# grissom_r1.net
KiCad netlist of a schematic drawn in EAGLE
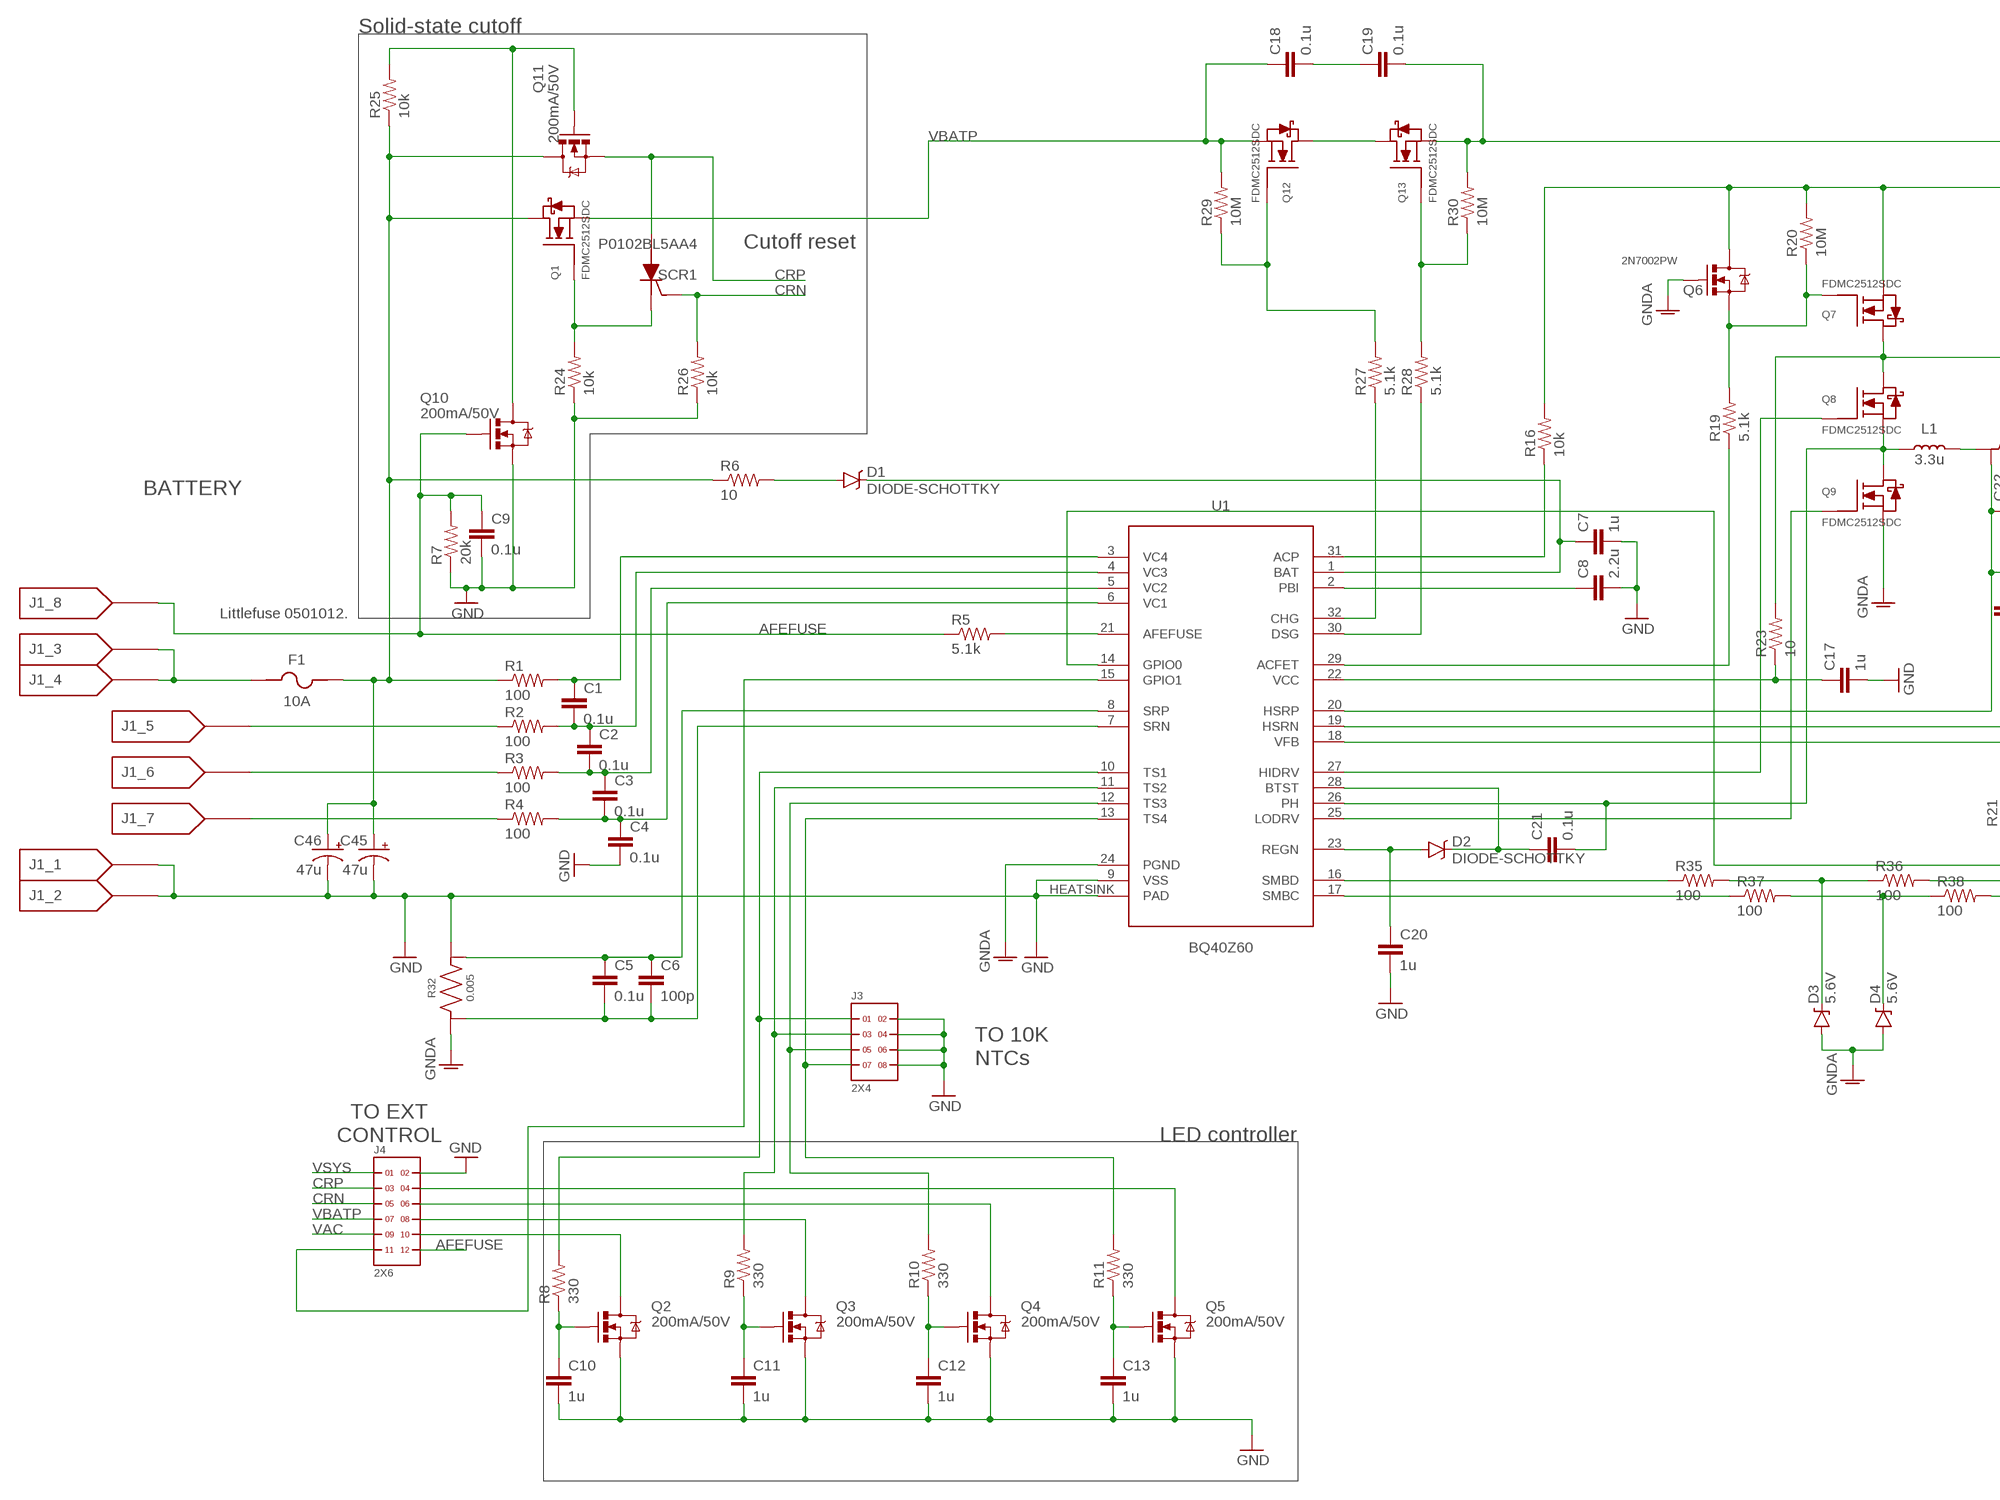
[diagram p0: schematic, sheet 1, part 1 of 2]
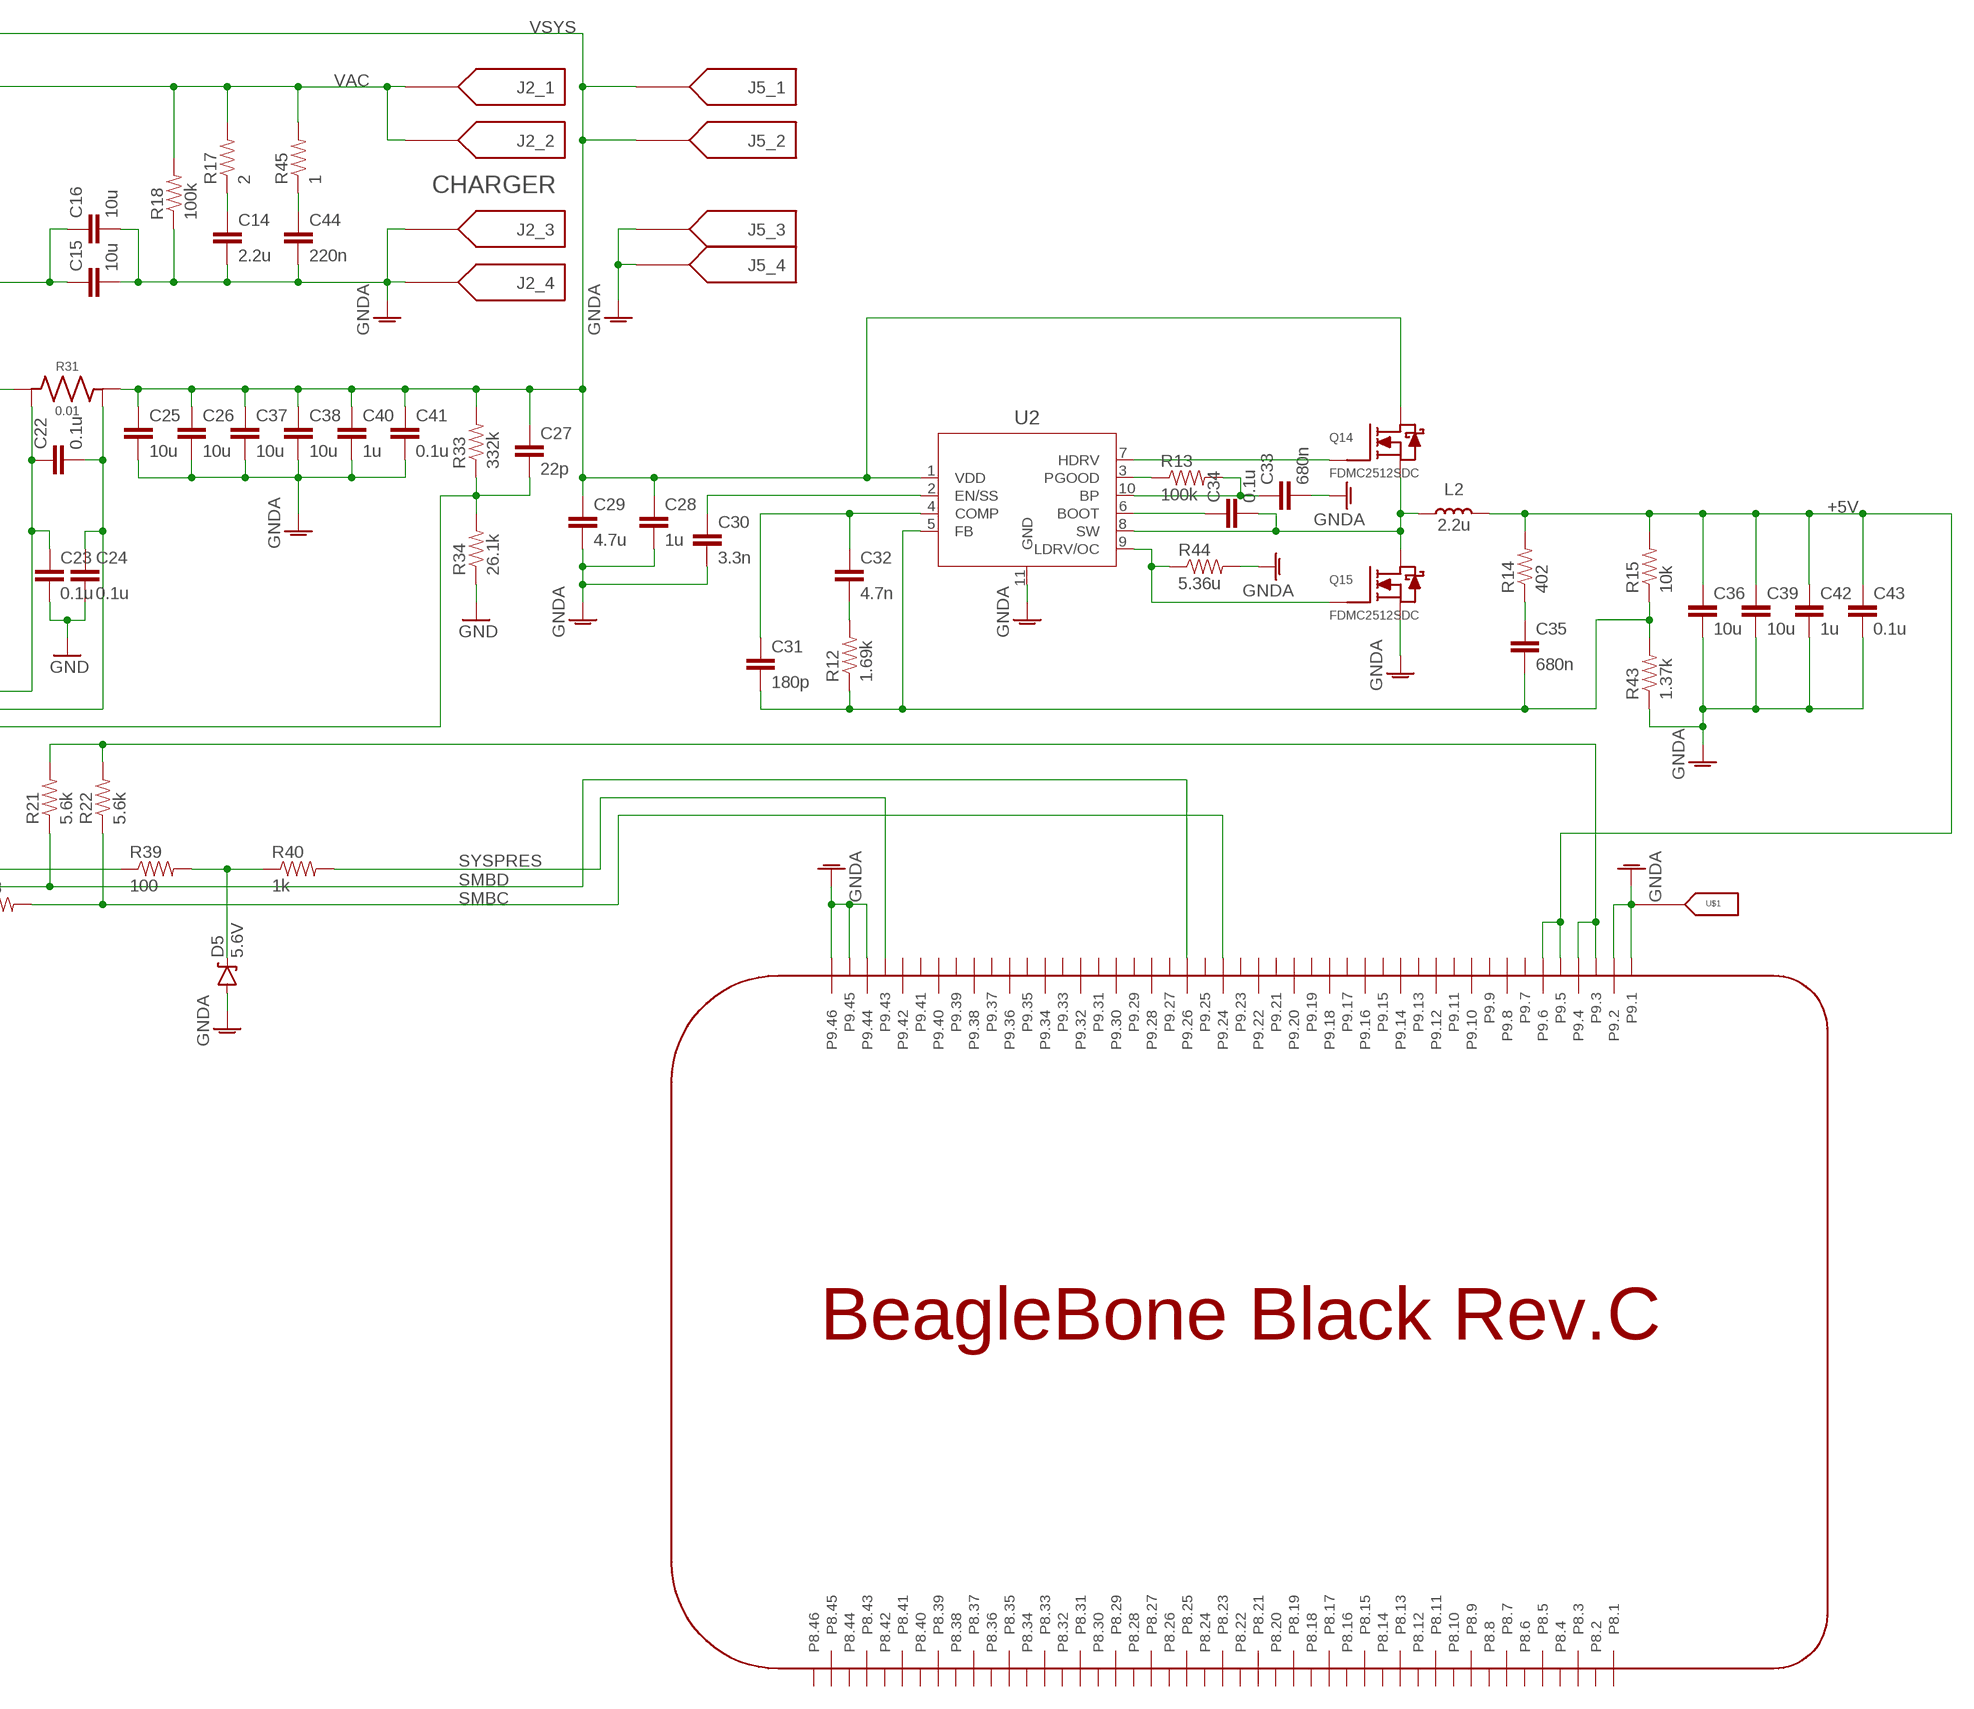
[diagram p1: schematic, sheet 1, part 2 of 2]

(export (version "E")
  (design (tool "Eeschema 10.0.6"))
  (components
    (comp (ref "C1")
      (value "0.1u")
      (footprint "eagle-import:0805")
      (libsource (lib "eagle-import") (part "CAP0805"))
    )
    (comp (ref "C2")
      (value "0.1u")
      (footprint "eagle-import:0805")
      (libsource (lib "eagle-import") (part "CAP0805"))
    )
    (comp (ref "C3")
      (value "0.1u")
      (footprint "eagle-import:0805")
      (libsource (lib "eagle-import") (part "CAP0805"))
    )
    (comp (ref "C4")
      (value "0.1u")
      (footprint "eagle-import:0805")
      (libsource (lib "eagle-import") (part "CAP0805"))
    )
    (comp (ref "C5")
      (value "0.1u")
      (footprint "eagle-import:0805")
      (libsource (lib "eagle-import") (part "CAP0805"))
    )
    (comp (ref "C6")
      (value "100p")
      (footprint "eagle-import:0805")
      (libsource (lib "eagle-import") (part "CAP0805"))
    )
    (comp (ref "C7")
      (value "1u")
      (footprint "eagle-import:0805")
      (libsource (lib "eagle-import") (part "CAP0805"))
    )
    (comp (ref "C8")
      (value "2.2u")
      (footprint "eagle-import:0805")
      (libsource (lib "eagle-import") (part "CAP0805"))
    )
    (comp (ref "C9")
      (value "0.1u")
      (footprint "eagle-import:0805")
      (libsource (lib "eagle-import") (part "CAP0805"))
    )
    (comp (ref "C10")
      (value "1u")
      (footprint "eagle-import:0805")
      (libsource (lib "eagle-import") (part "CAP0805"))
    )
    (comp (ref "C11")
      (value "1u")
      (footprint "eagle-import:0805")
      (libsource (lib "eagle-import") (part "CAP0805"))
    )
    (comp (ref "C12")
      (value "1u")
      (footprint "eagle-import:0805")
      (libsource (lib "eagle-import") (part "CAP0805"))
    )
    (comp (ref "C13")
      (value "1u")
      (footprint "eagle-import:0805")
      (libsource (lib "eagle-import") (part "CAP0805"))
    )
    (comp (ref "C14")
      (value "2.2u")
      (footprint "eagle-import:0805")
      (libsource (lib "eagle-import") (part "CAP0805"))
    )
    (comp (ref "C15")
      (value "10u")
      (footprint "eagle-import:1206")
      (libsource (lib "eagle-import") (part "CAP1206"))
    )
    (comp (ref "C16")
      (value "10u")
      (footprint "eagle-import:1206")
      (libsource (lib "eagle-import") (part "CAP1206"))
    )
    (comp (ref "C17")
      (value "1u")
      (footprint "eagle-import:0805")
      (libsource (lib "eagle-import") (part "CAP0805"))
    )
    (comp (ref "C18")
      (value "0.1u")
      (footprint "eagle-import:0805")
      (libsource (lib "eagle-import") (part "CAP0805"))
    )
    (comp (ref "C19")
      (value "0.1u")
      (footprint "eagle-import:0805")
      (libsource (lib "eagle-import") (part "CAP0805"))
    )
    (comp (ref "C20")
      (value "1u")
      (footprint "eagle-import:0805")
      (libsource (lib "eagle-import") (part "CAP0805"))
    )
    (comp (ref "C21")
      (value "0.1u")
      (footprint "eagle-import:0805")
      (libsource (lib "eagle-import") (part "CAP0805"))
    )
    (comp (ref "C22")
      (value "0.1u")
      (footprint "eagle-import:0805")
      (libsource (lib "eagle-import") (part "CAP0805"))
    )
    (comp (ref "C23")
      (value "0.1u")
      (footprint "eagle-import:0805")
      (libsource (lib "eagle-import") (part "CAP0805"))
    )
    (comp (ref "C24")
      (value "0.1u")
      (footprint "eagle-import:0805")
      (libsource (lib "eagle-import") (part "CAP0805"))
    )
    (comp (ref "C25")
      (value "10u")
      (footprint "eagle-import:1206")
      (libsource (lib "eagle-import") (part "CAP1206"))
    )
    (comp (ref "C26")
      (value "10u")
      (footprint "eagle-import:1206")
      (libsource (lib "eagle-import") (part "CAP1206"))
    )
    (comp (ref "C27")
      (value "22p")
      (footprint "eagle-import:0805")
      (libsource (lib "eagle-import") (part "CAP0805"))
    )
    (comp (ref "C28")
      (value "1u")
      (footprint "eagle-import:0805")
      (libsource (lib "eagle-import") (part "CAP0805"))
    )
    (comp (ref "C29")
      (value "4.7u")
      (footprint "eagle-import:0805")
      (libsource (lib "eagle-import") (part "CAP0805"))
    )
    (comp (ref "C30")
      (value "3.3n")
      (footprint "eagle-import:0805")
      (libsource (lib "eagle-import") (part "CAP0805"))
    )
    (comp (ref "C31")
      (value "180p")
      (footprint "eagle-import:0805")
      (libsource (lib "eagle-import") (part "CAP0805"))
    )
    (comp (ref "C32")
      (value "4.7n")
      (footprint "eagle-import:0805")
      (libsource (lib "eagle-import") (part "CAP0805"))
    )
    (comp (ref "C33")
      (value "680n")
      (footprint "eagle-import:0805")
      (libsource (lib "eagle-import") (part "CAP0805"))
    )
    (comp (ref "C34")
      (value "0.1u")
      (footprint "eagle-import:0805")
      (libsource (lib "eagle-import") (part "CAP0805"))
    )
    (comp (ref "C35")
      (value "680n")
      (footprint "eagle-import:0805")
      (libsource (lib "eagle-import") (part "CAP0805"))
    )
    (comp (ref "C36")
      (value "10u")
      (footprint "eagle-import:1206")
      (libsource (lib "eagle-import") (part "CAP1206"))
    )
    (comp (ref "C37")
      (value "10u")
      (footprint "eagle-import:1206")
      (libsource (lib "eagle-import") (part "CAP1206"))
    )
    (comp (ref "C38")
      (value "10u")
      (footprint "eagle-import:1206")
      (libsource (lib "eagle-import") (part "CAP1206"))
    )
    (comp (ref "C39")
      (value "10u")
      (footprint "eagle-import:1206")
      (libsource (lib "eagle-import") (part "CAP1206"))
    )
    (comp (ref "C40")
      (value "1u")
      (footprint "eagle-import:1206")
      (libsource (lib "eagle-import") (part "CAP1206"))
    )
    (comp (ref "C41")
      (value "0.1u")
      (footprint "eagle-import:1206")
      (libsource (lib "eagle-import") (part "CAP1206"))
    )
    (comp (ref "C42")
      (value "1u")
      (footprint "eagle-import:1206")
      (libsource (lib "eagle-import") (part "CAP1206"))
    )
    (comp (ref "C43")
      (value "0.1u")
      (footprint "eagle-import:1206")
      (libsource (lib "eagle-import") (part "CAP1206"))
    )
    (comp (ref "C44")
      (value "220n")
      (footprint "eagle-import:0805")
      (libsource (lib "eagle-import") (part "CAP0805"))
    )
    (comp (ref "C45")
      (value "47u")
      (footprint "eagle-import:CPOL-RADIAL-10UF-25V")
      (libsource (lib "eagle-import") (part "CAP_POLPTH2"))
    )
    (comp (ref "C46")
      (value "47u")
      (footprint "eagle-import:CPOL-RADIAL-10UF-25V")
      (libsource (lib "eagle-import") (part "CAP_POLPTH2"))
    )
    (comp (ref "D1")
      (value "DIODE-SCHOTTKY")
      (footprint "eagle-import:SOT23-3")
      (libsource (lib "eagle-import") (part "DIODE-SCHOTTKY"))
    )
    (comp (ref "D2")
      (value "DIODE-SCHOTTKY")
      (footprint "eagle-import:SOT23-3")
      (libsource (lib "eagle-import") (part "DIODE-SCHOTTKY"))
    )
    (comp (ref "D3")
      (value "5.6V")
      (footprint "eagle-import:SOD-323")
      (libsource (lib "eagle-import") (part "DIODE-ZENER5.6V"))
    )
    (comp (ref "D4")
      (value "5.6V")
      (footprint "eagle-import:SOD-323")
      (libsource (lib "eagle-import") (part "DIODE-ZENER5.6V"))
    )
    (comp (ref "D5")
      (value "5.6V")
      (footprint "eagle-import:SOD-323")
      (libsource (lib "eagle-import") (part "DIODE-ZENER5.6V"))
    )
    (comp (ref "F1")
      (value "10A")
      (footprint "eagle-import:LITTELFUSE_501")
      (libsource (lib "eagle-import") (part "LITTELFUSE_501"))
    )
    (comp (ref "J1")
      (value "105314-X208")
      (footprint "eagle-import:105314-X208")
      (libsource (lib "eagle-import") (part "105314-X208"))
    )
    (comp (ref "J2")
      (value "105314-X204")
      (footprint "eagle-import:105314-X204")
      (libsource (lib "eagle-import") (part "105314-X204"))
    )
    (comp (ref "J3")
      (value "2X4")
      (footprint "eagle-import:2X4")
      (libsource (lib "eagle-import") (part "2X4"))
    )
    (comp (ref "J4")
      (value "2X6")
      (footprint "eagle-import:2X6")
      (libsource (lib "eagle-import") (part "2X6"))
    )
    (comp (ref "J5")
      (value "105314-X204")
      (footprint "eagle-import:105314-X204")
      (libsource (lib "eagle-import") (part "105314-X204"))
    )
    (comp (ref "L1")
      (value "3.3u")
      (footprint "eagle-import:BOURNS_SRP7028A")
      (libsource (lib "eagle-import") (part "BOURNS_SRP7028A"))
    )
    (comp (ref "L2")
      (value "2.2u")
      (footprint "eagle-import:BOURNS_SRP7028A")
      (libsource (lib "eagle-import") (part "BOURNS_SRP7028A"))
    )
    (comp (ref "PCB1")
      (value "BEAGLEBONE_BLACK_BLANK")
      (footprint "eagle-import:BEAGLEBONE_BLACK_BLANK")
      (libsource (lib "eagle-import") (part "BEAGLEBONE_BLACK_BLANK"))
    )
    (comp (ref "Q1")
      (value "FDMC2512SDC")
      (footprint "eagle-import:MO240")
      (libsource (lib "eagle-import") (part "FDMC2512SDC"))
    )
    (comp (ref "Q2")
      (value "200mA/50V")
      (footprint "eagle-import:SOT23-3")
      (libsource (lib "eagle-import") (part "MOSFET-NCHANNELBSS138"))
    )
    (comp (ref "Q3")
      (value "200mA/50V")
      (footprint "eagle-import:SOT23-3")
      (libsource (lib "eagle-import") (part "MOSFET-NCHANNELBSS138"))
    )
    (comp (ref "Q4")
      (value "200mA/50V")
      (footprint "eagle-import:SOT23-3")
      (libsource (lib "eagle-import") (part "MOSFET-NCHANNELBSS138"))
    )
    (comp (ref "Q5")
      (value "200mA/50V")
      (footprint "eagle-import:SOT23-3")
      (libsource (lib "eagle-import") (part "MOSFET-NCHANNELBSS138"))
    )
    (comp (ref "Q6")
      (value "2N7002PW")
      (footprint "eagle-import:SOT323")
      (libsource (lib "eagle-import") (part "MOSFET-NCHANNEL2N7002PW"))
    )
    (comp (ref "Q7")
      (value "FDMC2512SDC")
      (footprint "eagle-import:MO240")
      (libsource (lib "eagle-import") (part "FDMC2512SDC"))
    )
    (comp (ref "Q8")
      (value "FDMC2512SDC")
      (footprint "eagle-import:MO240")
      (libsource (lib "eagle-import") (part "FDMC2512SDC"))
    )
    (comp (ref "Q9")
      (value "FDMC2512SDC")
      (footprint "eagle-import:MO240")
      (libsource (lib "eagle-import") (part "FDMC2512SDC"))
    )
    (comp (ref "Q10")
      (value "200mA/50V")
      (footprint "eagle-import:SOT23-3")
      (libsource (lib "eagle-import") (part "MOSFET-NCHANNELBSS138"))
    )
    (comp (ref "Q11")
      (value "200mA/50V")
      (footprint "eagle-import:SOT23-3")
      (libsource (lib "eagle-import") (part "MOSFET-NCHANNELBSS138"))
    )
    (comp (ref "Q12")
      (value "FDMC2512SDC")
      (footprint "eagle-import:MO240")
      (libsource (lib "eagle-import") (part "FDMC2512SDC"))
    )
    (comp (ref "Q13")
      (value "FDMC2512SDC")
      (footprint "eagle-import:MO240")
      (libsource (lib "eagle-import") (part "FDMC2512SDC"))
    )
    (comp (ref "Q14")
      (value "FDMC2512SDC")
      (footprint "eagle-import:MO240")
      (libsource (lib "eagle-import") (part "FDMC2512SDC"))
    )
    (comp (ref "Q15")
      (value "FDMC2512SDC")
      (footprint "eagle-import:MO240")
      (libsource (lib "eagle-import") (part "FDMC2512SDC"))
    )
    (comp (ref "R1")
      (value "100")
      (footprint "eagle-import:0805")
      (libsource (lib "eagle-import") (part "RESISTOR0805-RES"))
    )
    (comp (ref "R2")
      (value "100")
      (footprint "eagle-import:0805")
      (libsource (lib "eagle-import") (part "RESISTOR0805-RES"))
    )
    (comp (ref "R3")
      (value "100")
      (footprint "eagle-import:0805")
      (libsource (lib "eagle-import") (part "RESISTOR0805-RES"))
    )
    (comp (ref "R4")
      (value "100")
      (footprint "eagle-import:0805")
      (libsource (lib "eagle-import") (part "RESISTOR0805-RES"))
    )
    (comp (ref "R5")
      (value "5.1k")
      (footprint "eagle-import:0805")
      (libsource (lib "eagle-import") (part "RESISTOR0805-RES"))
    )
    (comp (ref "R6")
      (value "10")
      (footprint "eagle-import:1206")
      (libsource (lib "eagle-import") (part "RESISTOR1206"))
    )
    (comp (ref "R7")
      (value "20k")
      (footprint "eagle-import:0805")
      (libsource (lib "eagle-import") (part "RESISTOR0805-RES"))
    )
    (comp (ref "R8")
      (value "330")
      (footprint "eagle-import:0805")
      (libsource (lib "eagle-import") (part "RESISTOR0805-RES"))
    )
    (comp (ref "R9")
      (value "330")
      (footprint "eagle-import:0805")
      (libsource (lib "eagle-import") (part "RESISTOR0805-RES"))
    )
    (comp (ref "R10")
      (value "330")
      (footprint "eagle-import:0805")
      (libsource (lib "eagle-import") (part "RESISTOR0805-RES"))
    )
    (comp (ref "R11")
      (value "330")
      (footprint "eagle-import:0805")
      (libsource (lib "eagle-import") (part "RESISTOR0805-RES"))
    )
    (comp (ref "R12")
      (value "1.69k")
      (footprint "eagle-import:0805")
      (libsource (lib "eagle-import") (part "RESISTOR0805-RES"))
    )
    (comp (ref "R13")
      (value "100k")
      (footprint "eagle-import:0805")
      (libsource (lib "eagle-import") (part "RESISTOR0805-RES"))
    )
    (comp (ref "R14")
      (value "402")
      (footprint "eagle-import:0805")
      (libsource (lib "eagle-import") (part "RESISTOR0805-RES"))
    )
    (comp (ref "R15")
      (value "10k")
      (footprint "eagle-import:0805")
      (libsource (lib "eagle-import") (part "RESISTOR0805-RES"))
    )
    (comp (ref "R16")
      (value "10k")
      (footprint "eagle-import:0805")
      (libsource (lib "eagle-import") (part "RESISTOR0805-RES"))
    )
    (comp (ref "R17")
      (value "2")
      (footprint "eagle-import:0805")
      (libsource (lib "eagle-import") (part "RESISTOR0805-RES"))
    )
    (comp (ref "R18")
      (value "100k")
      (footprint "eagle-import:0805")
      (libsource (lib "eagle-import") (part "RESISTOR0805-RES"))
    )
    (comp (ref "R19")
      (value "5.1k")
      (footprint "eagle-import:0805")
      (libsource (lib "eagle-import") (part "RESISTOR0805-RES"))
    )
    (comp (ref "R20")
      (value "10M")
      (footprint "eagle-import:0805")
      (libsource (lib "eagle-import") (part "RESISTOR0805-RES"))
    )
    (comp (ref "R21")
      (value "5.6k")
      (footprint "eagle-import:0805")
      (libsource (lib "eagle-import") (part "RESISTOR0805-RES"))
    )
    (comp (ref "R22")
      (value "5.6k")
      (footprint "eagle-import:0805")
      (libsource (lib "eagle-import") (part "RESISTOR0805-RES"))
    )
    (comp (ref "R23")
      (value "10")
      (footprint "eagle-import:0805")
      (libsource (lib "eagle-import") (part "RESISTOR0805-RES"))
    )
    (comp (ref "R24")
      (value "10k")
      (footprint "eagle-import:0805")
      (libsource (lib "eagle-import") (part "RESISTOR0805-RES"))
    )
    (comp (ref "R25")
      (value "10k")
      (footprint "eagle-import:0805")
      (libsource (lib "eagle-import") (part "RESISTOR0805-RES"))
    )
    (comp (ref "R26")
      (value "10k")
      (footprint "eagle-import:0805")
      (libsource (lib "eagle-import") (part "RESISTOR0805-RES"))
    )
    (comp (ref "R27")
      (value "5.1k")
      (footprint "eagle-import:0805")
      (libsource (lib "eagle-import") (part "RESISTOR0805-RES"))
    )
    (comp (ref "R28")
      (value "5.1k")
      (footprint "eagle-import:0805")
      (libsource (lib "eagle-import") (part "RESISTOR0805-RES"))
    )
    (comp (ref "R29")
      (value "10M")
      (footprint "eagle-import:0805")
      (libsource (lib "eagle-import") (part "RESISTOR0805-RES"))
    )
    (comp (ref "R30")
      (value "10M")
      (footprint "eagle-import:0805")
      (libsource (lib "eagle-import") (part "RESISTOR0805-RES"))
    )
    (comp (ref "R31")
      (value "0.01")
      (footprint "eagle-import:1206_4T")
      (libsource (lib "eagle-import") (part "OHMITE_FC4L32"))
    )
    (comp (ref "R32")
      (value "0.005")
      (footprint "eagle-import:0612_4T")
      (libsource (lib "eagle-import") (part "VISHAY_WSK0612"))
    )
    (comp (ref "R33")
      (value "332k")
      (footprint "eagle-import:0805")
      (libsource (lib "eagle-import") (part "RESISTOR0805-RES"))
    )
    (comp (ref "R34")
      (value "26.1k")
      (footprint "eagle-import:0805")
      (libsource (lib "eagle-import") (part "RESISTOR0805-RES"))
    )
    (comp (ref "R35")
      (value "100")
      (footprint "eagle-import:0805")
      (libsource (lib "eagle-import") (part "RESISTOR0805-RES"))
    )
    (comp (ref "R36")
      (value "100")
      (footprint "eagle-import:0805")
      (libsource (lib "eagle-import") (part "RESISTOR0805-RES"))
    )
    (comp (ref "R37")
      (value "100")
      (footprint "eagle-import:0805")
      (libsource (lib "eagle-import") (part "RESISTOR0805-RES"))
    )
    (comp (ref "R38")
      (value "100")
      (footprint "eagle-import:0805")
      (libsource (lib "eagle-import") (part "RESISTOR0805-RES"))
    )
    (comp (ref "R39")
      (value "100")
      (footprint "eagle-import:0805")
      (libsource (lib "eagle-import") (part "RESISTOR0805-RES"))
    )
    (comp (ref "R40")
      (value "1k")
      (footprint "eagle-import:0805")
      (libsource (lib "eagle-import") (part "RESISTOR0805-RES"))
    )
    (comp (ref "R43")
      (value "1.37k")
      (footprint "eagle-import:0805")
      (libsource (lib "eagle-import") (part "RESISTOR0805-RES"))
    )
    (comp (ref "R44")
      (value "5.36u")
      (footprint "eagle-import:0805")
      (libsource (lib "eagle-import") (part "RESISTOR0805-RES"))
    )
    (comp (ref "R45")
      (value "1")
      (footprint "eagle-import:0805")
      (libsource (lib "eagle-import") (part "RESISTOR0805-RES"))
    )
    (comp (ref "SCR1")
      (value "P0102BL5AA4")
      (footprint "eagle-import:SOT23-3")
      (libsource (lib "eagle-import") (part "P0102BL5AA4"))
    )
    (comp (ref "U$1")
      (value "SU_LOGO-DUMMY2")
      (footprint "eagle-import:SU_LOGO_SS")
      (libsource (lib "eagle-import") (part "SU_LOGO-DUMMY2"))
    )
    (comp (ref "U1")
      (value "BQ40Z60")
      (footprint "eagle-import:QFN32")
      (libsource (lib "eagle-import") (part "BQ40Z60"))
    )
    (comp (ref "U2")
      (value "TPS40305DRCR")
      (footprint "eagle-import:S-PVSON-N10")
      (libsource (lib "eagle-import") (part "TPS40305DRCR"))
    )
  )
  (nets
    (net (code "1") (name "/+5V") (class "Default")
      (node (ref "C36") (pin "1") (pinfunction "1_1") (pintype "passive"))
      (node (ref "C39") (pin "1") (pinfunction "1_1") (pintype "passive"))
      (node (ref "C42") (pin "1") (pinfunction "1_1") (pintype "passive"))
      (node (ref "C43") (pin "1") (pinfunction "1_1") (pintype "passive"))
      (node (ref "L2") (pin "P$2") (pinfunction "P$2_P$2") (pintype "bidirectional"))
      (node (ref "PCB1") (pin "P9.5") (pinfunction "P9.5_P9.5") (pintype "bidirectional"))
      (node (ref "PCB1") (pin "P9.6") (pinfunction "P9.6_P9.6") (pintype "bidirectional"))
      (node (ref "R14") (pin "2") (pinfunction "2_2") (pintype "passive"))
      (node (ref "R15") (pin "2") (pinfunction "2_2") (pintype "passive"))
    )
    (net (code "2") (name "/AFEFUSE") (class "Default")
      (node (ref "C9") (pin "1") (pinfunction "1_1") (pintype "passive"))
      (node (ref "J1") (pin "P$8") (pinfunction "P$1_P$8") (pintype "bidirectional"))
      (node (ref "J4") (pin "12") (pinfunction "12_12") (pintype "bidirectional"))
      (node (ref "Q10") (pin "1") (pinfunction "G_1") (pintype "passive"))
      (node (ref "R5") (pin "1") (pinfunction "1_1") (pintype "passive"))
      (node (ref "R7") (pin "2") (pinfunction "2_2") (pintype "passive"))
    )
    (net (code "3") (name "/CRN") (class "Default")
      (node (ref "J4") (pin "5") (pinfunction "5_5") (pintype "bidirectional"))
      (node (ref "R26") (pin "2") (pinfunction "2_2") (pintype "passive"))
      (node (ref "SCR1") (pin "2") (pinfunction "G_2") (pintype "bidirectional"))
    )
    (net (code "4") (name "/CRP") (class "Default")
      (node (ref "J4") (pin "3") (pinfunction "3_3") (pintype "bidirectional"))
      (node (ref "Q11") (pin "2") (pinfunction "S_2") (pintype "passive"))
      (node (ref "SCR1") (pin "3") (pinfunction "A_3") (pintype "bidirectional"))
    )
    (net (code "5") (name "/VAC") (class "Default")
      (node (ref "J2") (pin "P$1") (pinfunction "P$1_P$1") (pintype "bidirectional"))
      (node (ref "J2") (pin "P$2") (pinfunction "P$1_P$2") (pintype "bidirectional"))
      (node (ref "J4") (pin "9") (pinfunction "9_9") (pintype "bidirectional"))
      (node (ref "Q6") (pin "3") (pinfunction "D_3") (pintype "passive"))
      (node (ref "Q7") (pin "P$1") (pinfunction "S_P$1") (pintype "bidirectional"))
      (node (ref "Q7") (pin "P$2") (pinfunction "S_P$2") (pintype "bidirectional"))
      (node (ref "Q7") (pin "P$3") (pinfunction "S_P$3") (pintype "bidirectional"))
      (node (ref "R16") (pin "2") (pinfunction "2_2") (pintype "passive"))
      (node (ref "R17") (pin "2") (pinfunction "2_2") (pintype "passive"))
      (node (ref "R18") (pin "2") (pinfunction "2_2") (pintype "passive"))
      (node (ref "R20") (pin "2") (pinfunction "2_2") (pintype "passive"))
      (node (ref "R45") (pin "2") (pinfunction "2_2") (pintype "passive"))
    )
    (net (code "6") (name "/VBATP") (class "Default")
      (node (ref "C18") (pin "1") (pinfunction "1_1") (pintype "passive"))
      (node (ref "J4") (pin "7") (pinfunction "7_7") (pintype "bidirectional"))
      (node (ref "Q1") (pin "P$1") (pinfunction "S_P$1") (pintype "bidirectional"))
      (node (ref "Q1") (pin "P$2") (pinfunction "S_P$2") (pintype "bidirectional"))
      (node (ref "Q1") (pin "P$3") (pinfunction "S_P$3") (pintype "bidirectional"))
      (node (ref "Q12") (pin "P$1") (pinfunction "S_P$1") (pintype "bidirectional"))
      (node (ref "Q12") (pin "P$2") (pinfunction "S_P$2") (pintype "bidirectional"))
      (node (ref "Q12") (pin "P$3") (pinfunction "S_P$3") (pintype "bidirectional"))
      (node (ref "R29") (pin "2") (pinfunction "2_2") (pintype "passive"))
    )
    (net (code "7") (name "/VSYS") (class "Default")
      (node (ref "C19") (pin "2") (pinfunction "2_2") (pintype "passive"))
      (node (ref "C25") (pin "1") (pinfunction "1_1") (pintype "passive"))
      (node (ref "C26") (pin "1") (pinfunction "1_1") (pintype "passive"))
      (node (ref "C27") (pin "1") (pinfunction "1_1") (pintype "passive"))
      (node (ref "C28") (pin "1") (pinfunction "1_1") (pintype "passive"))
      (node (ref "C29") (pin "1") (pinfunction "1_1") (pintype "passive"))
      (node (ref "C37") (pin "1") (pinfunction "1_1") (pintype "passive"))
      (node (ref "C38") (pin "1") (pinfunction "1_1") (pintype "passive"))
      (node (ref "C40") (pin "1") (pinfunction "1_1") (pintype "passive"))
      (node (ref "C41") (pin "1") (pinfunction "1_1") (pintype "passive"))
      (node (ref "J4") (pin "1") (pinfunction "1_1") (pintype "bidirectional"))
      (node (ref "J5") (pin "P$1") (pinfunction "P$1_P$1") (pintype "bidirectional"))
      (node (ref "J5") (pin "P$2") (pinfunction "P$1_P$2") (pintype "bidirectional"))
      (node (ref "Q13") (pin "P$1") (pinfunction "S_P$1") (pintype "bidirectional"))
      (node (ref "Q13") (pin "P$2") (pinfunction "S_P$2") (pintype "bidirectional"))
      (node (ref "Q13") (pin "P$3") (pinfunction "S_P$3") (pintype "bidirectional"))
      (node (ref "Q14") (pin "P$5") (pinfunction "D_P$5") (pintype "bidirectional"))
      (node (ref "Q14") (pin "P$6") (pinfunction "D_P$6") (pintype "bidirectional"))
      (node (ref "Q14") (pin "P$7") (pinfunction "D_P$7") (pintype "bidirectional"))
      (node (ref "Q14") (pin "P$8") (pinfunction "D_P$8") (pintype "bidirectional"))
      (node (ref "Q14") (pin "PAD") (pinfunction "D_PAD") (pintype "bidirectional"))
      (node (ref "R30") (pin "2") (pinfunction "2_2") (pintype "passive"))
      (node (ref "R31") (pin "P$2") (pinfunction "P$2_P$2") (pintype "bidirectional"))
      (node (ref "R33") (pin "2") (pinfunction "2_2") (pintype "passive"))
      (node (ref "U2") (pin "1") (pinfunction "VDD_1") (pintype "passive"))
    )
    (net (code "8") (name "GND") (class "Default")
      (node (ref "C10") (pin "2") (pinfunction "2_2") (pintype "passive"))
      (node (ref "C11") (pin "2") (pinfunction "2_2") (pintype "passive"))
      (node (ref "C12") (pin "2") (pinfunction "2_2") (pintype "passive"))
      (node (ref "C13") (pin "2") (pinfunction "2_2") (pintype "passive"))
      (node (ref "C17") (pin "2") (pinfunction "2_2") (pintype "passive"))
      (node (ref "C20") (pin "2") (pinfunction "2_2") (pintype "passive"))
      (node (ref "C23") (pin "2") (pinfunction "2_2") (pintype "passive"))
      (node (ref "C24") (pin "2") (pinfunction "2_2") (pintype "passive"))
      (node (ref "C4") (pin "2") (pinfunction "2_2") (pintype "passive"))
      (node (ref "C45") (pin "2") (pinfunction "-_2") (pintype "passive"))
      (node (ref "C46") (pin "2") (pinfunction "-_2") (pintype "passive"))
      (node (ref "C7") (pin "2") (pinfunction "2_2") (pintype "passive"))
      (node (ref "C8") (pin "2") (pinfunction "2_2") (pintype "passive"))
      (node (ref "C9") (pin "2") (pinfunction "2_2") (pintype "passive"))
      (node (ref "J1") (pin "P$1") (pinfunction "P$1_P$1") (pintype "bidirectional"))
      (node (ref "J1") (pin "P$2") (pinfunction "P$1_P$2") (pintype "bidirectional"))
      (node (ref "J3") (pin "2") (pinfunction "2_2") (pintype "bidirectional"))
      (node (ref "J3") (pin "4") (pinfunction "4_4") (pintype "bidirectional"))
      (node (ref "J3") (pin "6") (pinfunction "6_6") (pintype "bidirectional"))
      (node (ref "J3") (pin "8") (pinfunction "8_8") (pintype "bidirectional"))
      (node (ref "J4") (pin "2") (pinfunction "2_2") (pintype "bidirectional"))
      (node (ref "Q10") (pin "2") (pinfunction "S_2") (pintype "passive"))
      (node (ref "Q2") (pin "2") (pinfunction "S_2") (pintype "passive"))
      (node (ref "Q3") (pin "2") (pinfunction "S_2") (pintype "passive"))
      (node (ref "Q4") (pin "2") (pinfunction "S_2") (pintype "passive"))
      (node (ref "Q5") (pin "2") (pinfunction "S_2") (pintype "passive"))
      (node (ref "R24") (pin "1") (pinfunction "1_1") (pintype "passive"))
      (node (ref "R26") (pin "1") (pinfunction "1_1") (pintype "passive"))
      (node (ref "R32") (pin "P$2") (pinfunction "P$2_P$2") (pintype "bidirectional"))
      (node (ref "R34") (pin "1") (pinfunction "1_1") (pintype "passive"))
      (node (ref "R7") (pin "1") (pinfunction "1_1") (pintype "passive"))
      (node (ref "U1") (pin "9") (pinfunction "VSS_9") (pintype "bidirectional"))
      (node (ref "U1") (pin "HEATSINK") (pinfunction "PAD_HEATSINK") (pintype "bidirectional"))
    )
    (net (code "9") (name "GNDA") (class "Default")
      (node (ref "C14") (pin "2") (pinfunction "2_2") (pintype "passive"))
      (node (ref "C15") (pin "2") (pinfunction "2_2") (pintype "passive"))
      (node (ref "C16") (pin "2") (pinfunction "2_2") (pintype "passive"))
      (node (ref "C25") (pin "2") (pinfunction "2_2") (pintype "passive"))
      (node (ref "C26") (pin "2") (pinfunction "2_2") (pintype "passive"))
      (node (ref "C28") (pin "2") (pinfunction "2_2") (pintype "passive"))
      (node (ref "C29") (pin "2") (pinfunction "2_2") (pintype "passive"))
      (node (ref "C30") (pin "2") (pinfunction "2_2") (pintype "passive"))
      (node (ref "C33") (pin "2") (pinfunction "2_2") (pintype "passive"))
      (node (ref "C36") (pin "2") (pinfunction "2_2") (pintype "passive"))
      (node (ref "C37") (pin "2") (pinfunction "2_2") (pintype "passive"))
      (node (ref "C38") (pin "2") (pinfunction "2_2") (pintype "passive"))
      (node (ref "C39") (pin "2") (pinfunction "2_2") (pintype "passive"))
      (node (ref "C40") (pin "2") (pinfunction "2_2") (pintype "passive"))
      (node (ref "C41") (pin "2") (pinfunction "2_2") (pintype "passive"))
      (node (ref "C42") (pin "2") (pinfunction "2_2") (pintype "passive"))
      (node (ref "C43") (pin "2") (pinfunction "2_2") (pintype "passive"))
      (node (ref "C44") (pin "2") (pinfunction "2_2") (pintype "passive"))
      (node (ref "D3") (pin "A") (pinfunction "A_A") (pintype "passive"))
      (node (ref "D4") (pin "A") (pinfunction "A_A") (pintype "passive"))
      (node (ref "D5") (pin "A") (pinfunction "A_A") (pintype "passive"))
      (node (ref "J2") (pin "P$3") (pinfunction "P$1_P$3") (pintype "bidirectional"))
      (node (ref "J2") (pin "P$4") (pinfunction "P$1_P$4") (pintype "bidirectional"))
      (node (ref "J5") (pin "P$3") (pinfunction "P$1_P$3") (pintype "bidirectional"))
      (node (ref "J5") (pin "P$4") (pinfunction "P$1_P$4") (pintype "bidirectional"))
      (node (ref "PCB1") (pin "P9.1") (pinfunction "P9.1_P9.1") (pintype "bidirectional"))
      (node (ref "PCB1") (pin "P9.2") (pinfunction "P9.2_P9.2") (pintype "bidirectional"))
      (node (ref "PCB1") (pin "P9.44") (pinfunction "P9.44_P9.44") (pintype "bidirectional"))
      (node (ref "PCB1") (pin "P9.45") (pinfunction "P9.45_P9.45") (pintype "bidirectional"))
      (node (ref "PCB1") (pin "P9.46") (pinfunction "P9.46_P9.46") (pintype "bidirectional"))
      (node (ref "Q15") (pin "P$1") (pinfunction "S_P$1") (pintype "bidirectional"))
      (node (ref "Q15") (pin "P$2") (pinfunction "S_P$2") (pintype "bidirectional"))
      (node (ref "Q15") (pin "P$3") (pinfunction "S_P$3") (pintype "bidirectional"))
      (node (ref "Q6") (pin "1") (pinfunction "G_1") (pintype "passive"))
      (node (ref "Q9") (pin "P$1") (pinfunction "S_P$1") (pintype "bidirectional"))
      (node (ref "Q9") (pin "P$2") (pinfunction "S_P$2") (pintype "bidirectional"))
      (node (ref "Q9") (pin "P$3") (pinfunction "S_P$3") (pintype "bidirectional"))
      (node (ref "R18") (pin "1") (pinfunction "1_1") (pintype "passive"))
      (node (ref "R32") (pin "P$1") (pinfunction "P$1_P$1") (pintype "bidirectional"))
      (node (ref "R43") (pin "1") (pinfunction "1_1") (pintype "passive"))
      (node (ref "R44") (pin "2") (pinfunction "2_2") (pintype "passive"))
      (node (ref "U$1") (pin "P$1") (pinfunction "P$1_P$1") (pintype "bidirectional"))
      (node (ref "U1") (pin "24") (pinfunction "PGND_24") (pintype "bidirectional"))
      (node (ref "U2") (pin "11") (pinfunction "GND_11") (pintype "passive"))
    )
    (net (code "10") (name "Net-(C14-Pad1)") (class "Default")
      (node (ref "C14") (pin "1") (pinfunction "1_1") (pintype "passive"))
      (node (ref "R17") (pin "1") (pinfunction "1_1") (pintype "passive"))
    )
    (net (code "11") (name "Net-(C15-Pad1)") (class "Default")
      (node (ref "C15") (pin "1") (pinfunction "1_1") (pintype "passive"))
      (node (ref "C16") (pin "1") (pinfunction "1_1") (pintype "passive"))
      (node (ref "Q7") (pin "P$5") (pinfunction "D_P$5") (pintype "bidirectional"))
      (node (ref "Q7") (pin "P$6") (pinfunction "D_P$6") (pintype "bidirectional"))
      (node (ref "Q7") (pin "P$7") (pinfunction "D_P$7") (pintype "bidirectional"))
      (node (ref "Q7") (pin "P$8") (pinfunction "D_P$8") (pintype "bidirectional"))
      (node (ref "Q7") (pin "PAD") (pinfunction "D_PAD") (pintype "bidirectional"))
      (node (ref "Q8") (pin "P$5") (pinfunction "D_P$5") (pintype "bidirectional"))
      (node (ref "Q8") (pin "P$6") (pinfunction "D_P$6") (pintype "bidirectional"))
      (node (ref "Q8") (pin "P$7") (pinfunction "D_P$7") (pintype "bidirectional"))
      (node (ref "Q8") (pin "P$8") (pinfunction "D_P$8") (pintype "bidirectional"))
      (node (ref "Q8") (pin "PAD") (pinfunction "D_PAD") (pintype "bidirectional"))
      (node (ref "R23") (pin "2") (pinfunction "2_2") (pintype "passive"))
    )
    (net (code "12") (name "Net-(C18-Pad2)") (class "Default")
      (node (ref "C18") (pin "2") (pinfunction "2_2") (pintype "passive"))
      (node (ref "C19") (pin "1") (pinfunction "1_1") (pintype "passive"))
    )
    (net (code "13") (name "Net-(C32-Pad2)") (class "Default")
      (node (ref "C32") (pin "2") (pinfunction "2_2") (pintype "passive"))
      (node (ref "R12") (pin "2") (pinfunction "2_2") (pintype "passive"))
    )
    (net (code "14") (name "Net-(C35-Pad1)") (class "Default")
      (node (ref "C35") (pin "1") (pinfunction "1_1") (pintype "passive"))
      (node (ref "R14") (pin "1") (pinfunction "1_1") (pintype "passive"))
    )
    (net (code "15") (name "Net-(C44-Pad1)") (class "Default")
      (node (ref "C44") (pin "1") (pinfunction "1_1") (pintype "passive"))
      (node (ref "R45") (pin "1") (pinfunction "1_1") (pintype "passive"))
    )
    (net (code "16") (name "Net-(C45-+)") (class "Default")
      (node (ref "C45") (pin "1") (pinfunction "+_1") (pintype "passive"))
      (node (ref "C46") (pin "1") (pinfunction "+_1") (pintype "passive"))
      (node (ref "F1") (pin "P$2") (pinfunction "P$2_P$2") (pintype "bidirectional"))
      (node (ref "Q1") (pin "P$5") (pinfunction "D_P$5") (pintype "bidirectional"))
      (node (ref "Q1") (pin "P$6") (pinfunction "D_P$6") (pintype "bidirectional"))
      (node (ref "Q1") (pin "P$7") (pinfunction "D_P$7") (pintype "bidirectional"))
      (node (ref "Q1") (pin "P$8") (pinfunction "D_P$8") (pintype "bidirectional"))
      (node (ref "Q1") (pin "PAD") (pinfunction "D_PAD") (pintype "bidirectional"))
      (node (ref "Q11") (pin "3") (pinfunction "D_3") (pintype "passive"))
      (node (ref "R1") (pin "1") (pinfunction "1_1") (pintype "passive"))
      (node (ref "R25") (pin "1") (pinfunction "1_1") (pintype "passive"))
      (node (ref "R6") (pin "1") (pinfunction "1_1") (pintype "passive"))
    )
    (net (code "17") (name "Net-(D1-A-Pad1)") (class "Default")
      (node (ref "D1") (pin "1") (pinfunction "A_1") (pintype "passive"))
      (node (ref "D1") (pin "2") (pinfunction "A_2") (pintype "passive"))
      (node (ref "R6") (pin "2") (pinfunction "2_2") (pintype "passive"))
    )
    (net (code "18") (name "Net-(D1-C)") (class "Default")
      (node (ref "C7") (pin "1") (pinfunction "1_1") (pintype "passive"))
      (node (ref "D1") (pin "3") (pinfunction "C_3") (pintype "passive"))
      (node (ref "U1") (pin "1") (pinfunction "BAT_1") (pintype "bidirectional"))
    )
    (net (code "19") (name "Net-(D2-C)") (class "Default")
      (node (ref "C21") (pin "1") (pinfunction "1_1") (pintype "passive"))
      (node (ref "D2") (pin "3") (pinfunction "C_3") (pintype "passive"))
      (node (ref "U1") (pin "28") (pinfunction "BTST_28") (pintype "bidirectional"))
    )
    (net (code "20") (name "Net-(D3-PadC)") (class "Default")
      (node (ref "D3") (pin "C") (pinfunction "C_C") (pintype "passive"))
      (node (ref "R35") (pin "2") (pinfunction "2_2") (pintype "passive"))
      (node (ref "R36") (pin "1") (pinfunction "1_1") (pintype "passive"))
    )
    (net (code "21") (name "Net-(D4-PadC)") (class "Default")
      (node (ref "D4") (pin "C") (pinfunction "C_C") (pintype "passive"))
      (node (ref "R37") (pin "2") (pinfunction "2_2") (pintype "passive"))
      (node (ref "R38") (pin "1") (pinfunction "1_1") (pintype "passive"))
    )
    (net (code "22") (name "Net-(D5-PadC)") (class "Default")
      (node (ref "D5") (pin "C") (pinfunction "C_C") (pintype "passive"))
      (node (ref "R39") (pin "2") (pinfunction "2_2") (pintype "passive"))
      (node (ref "R40") (pin "1") (pinfunction "1_1") (pintype "passive"))
    )
    (net (code "23") (name "Net-(J1C-P$1)") (class "Default")
      (node (ref "F1") (pin "P$1") (pinfunction "P$1_P$1") (pintype "bidirectional"))
      (node (ref "J1") (pin "P$3") (pinfunction "P$1_P$3") (pintype "bidirectional"))
      (node (ref "J1") (pin "P$4") (pinfunction "P$1_P$4") (pintype "bidirectional"))
    )
    (net (code "24") (name "Net-(J1E-P$1)") (class "Default")
      (node (ref "J1") (pin "P$5") (pinfunction "P$1_P$5") (pintype "bidirectional"))
      (node (ref "R2") (pin "1") (pinfunction "1_1") (pintype "passive"))
    )
    (net (code "25") (name "Net-(J1F-P$1)") (class "Default")
      (node (ref "J1") (pin "P$6") (pinfunction "P$1_P$6") (pintype "bidirectional"))
      (node (ref "R3") (pin "1") (pinfunction "1_1") (pintype "passive"))
    )
    (net (code "26") (name "Net-(J1G-P$1)") (class "Default")
      (node (ref "J1") (pin "P$7") (pinfunction "P$1_P$7") (pintype "bidirectional"))
      (node (ref "R4") (pin "1") (pinfunction "1_1") (pintype "passive"))
    )
    (net (code "27") (name "Net-(L1-PadP$2)") (class "Default")
      (node (ref "L1") (pin "P$2") (pinfunction "P$2_P$2") (pintype "bidirectional"))
      (node (ref "R31") (pin "P$1") (pinfunction "P$1_P$1") (pintype "bidirectional"))
    )
    (net (code "28") (name "Net-(PCB1-PadP9.3)") (class "Default")
      (node (ref "PCB1") (pin "P9.3") (pinfunction "P9.3_P9.3") (pintype "bidirectional"))
      (node (ref "PCB1") (pin "P9.4") (pinfunction "P9.4_P9.4") (pintype "bidirectional"))
      (node (ref "R21") (pin "2") (pinfunction "2_2") (pintype "passive"))
      (node (ref "R22") (pin "2") (pinfunction "2_2") (pintype "passive"))
    )
    (net (code "29") (name "Net-(PCB1-PadP9.24)") (class "Default")
      (node (ref "PCB1") (pin "P9.24") (pinfunction "P9.24_P9.24") (pintype "bidirectional"))
      (node (ref "R22") (pin "1") (pinfunction "1_1") (pintype "passive"))
      (node (ref "R38") (pin "2") (pinfunction "2_2") (pintype "passive"))
    )
    (net (code "30") (name "Net-(PCB1-PadP9.26)") (class "Default")
      (node (ref "PCB1") (pin "P9.26") (pinfunction "P9.26_P9.26") (pintype "bidirectional"))
      (node (ref "R21") (pin "1") (pinfunction "1_1") (pintype "passive"))
      (node (ref "R36") (pin "2") (pinfunction "2_2") (pintype "passive"))
    )
    (net (code "31") (name "Net-(PCB1-PadP9.43)") (class "Default")
      (node (ref "PCB1") (pin "P9.43") (pinfunction "P9.43_P9.43") (pintype "bidirectional"))
      (node (ref "R40") (pin "2") (pinfunction "2_2") (pintype "passive"))
    )
    (net (code "32") (name "Net-(Q1-G)") (class "Default")
      (node (ref "Q1") (pin "P$4") (pinfunction "G_P$4") (pintype "bidirectional"))
      (node (ref "R24") (pin "2") (pinfunction "2_2") (pintype "passive"))
      (node (ref "SCR1") (pin "1") (pinfunction "K_1") (pintype "bidirectional"))
    )
    (net (code "33") (name "Net-(Q2-D)") (class "Default")
      (node (ref "J4") (pin "10") (pinfunction "10_10") (pintype "bidirectional"))
      (node (ref "Q2") (pin "3") (pinfunction "D_3") (pintype "passive"))
    )
    (net (code "34") (name "Net-(Q2-G)") (class "Default")
      (node (ref "C10") (pin "1") (pinfunction "1_1") (pintype "passive"))
      (node (ref "Q2") (pin "1") (pinfunction "G_1") (pintype "passive"))
      (node (ref "R8") (pin "1") (pinfunction "1_1") (pintype "passive"))
    )
    (net (code "35") (name "Net-(Q3-D)") (class "Default")
      (node (ref "J4") (pin "8") (pinfunction "8_8") (pintype "bidirectional"))
      (node (ref "Q3") (pin "3") (pinfunction "D_3") (pintype "passive"))
    )
    (net (code "36") (name "Net-(Q3-G)") (class "Default")
      (node (ref "C11") (pin "1") (pinfunction "1_1") (pintype "passive"))
      (node (ref "Q3") (pin "1") (pinfunction "G_1") (pintype "passive"))
      (node (ref "R9") (pin "1") (pinfunction "1_1") (pintype "passive"))
    )
    (net (code "37") (name "Net-(Q4-D)") (class "Default")
      (node (ref "J4") (pin "6") (pinfunction "6_6") (pintype "bidirectional"))
      (node (ref "Q4") (pin "3") (pinfunction "D_3") (pintype "passive"))
    )
    (net (code "38") (name "Net-(Q4-G)") (class "Default")
      (node (ref "C12") (pin "1") (pinfunction "1_1") (pintype "passive"))
      (node (ref "Q4") (pin "1") (pinfunction "G_1") (pintype "passive"))
      (node (ref "R10") (pin "1") (pinfunction "1_1") (pintype "passive"))
    )
    (net (code "39") (name "Net-(Q5-D)") (class "Default")
      (node (ref "J4") (pin "4") (pinfunction "4_4") (pintype "bidirectional"))
      (node (ref "Q5") (pin "3") (pinfunction "D_3") (pintype "passive"))
    )
    (net (code "40") (name "Net-(Q5-G)") (class "Default")
      (node (ref "C13") (pin "1") (pinfunction "1_1") (pintype "passive"))
      (node (ref "Q5") (pin "1") (pinfunction "G_1") (pintype "passive"))
      (node (ref "R11") (pin "1") (pinfunction "1_1") (pintype "passive"))
    )
    (net (code "41") (name "Net-(Q6-S)") (class "Default")
      (node (ref "Q6") (pin "2") (pinfunction "S_2") (pintype "passive"))
      (node (ref "Q7") (pin "P$4") (pinfunction "G_P$4") (pintype "bidirectional"))
      (node (ref "R19") (pin "2") (pinfunction "2_2") (pintype "passive"))
      (node (ref "R20") (pin "1") (pinfunction "1_1") (pintype "passive"))
    )
    (net (code "42") (name "Net-(Q8-G)") (class "Default")
      (node (ref "Q8") (pin "P$4") (pinfunction "G_P$4") (pintype "bidirectional"))
      (node (ref "U1") (pin "27") (pinfunction "HIDRV_27") (pintype "bidirectional"))
    )
    (net (code "43") (name "Net-(Q9-G)") (class "Default")
      (node (ref "Q9") (pin "P$4") (pinfunction "G_P$4") (pintype "bidirectional"))
      (node (ref "U1") (pin "25") (pinfunction "LODRV_25") (pintype "bidirectional"))
    )
    (net (code "44") (name "Net-(Q10-D)") (class "Default")
      (node (ref "Q10") (pin "3") (pinfunction "D_3") (pintype "passive"))
      (node (ref "Q11") (pin "1") (pinfunction "G_1") (pintype "passive"))
      (node (ref "R25") (pin "2") (pinfunction "2_2") (pintype "passive"))
    )
    (net (code "45") (name "Net-(Q12-D-PadP$5)") (class "Default")
      (node (ref "Q12") (pin "P$5") (pinfunction "D_P$5") (pintype "bidirectional"))
      (node (ref "Q12") (pin "P$6") (pinfunction "D_P$6") (pintype "bidirectional"))
      (node (ref "Q12") (pin "P$7") (pinfunction "D_P$7") (pintype "bidirectional"))
      (node (ref "Q12") (pin "P$8") (pinfunction "D_P$8") (pintype "bidirectional"))
      (node (ref "Q12") (pin "PAD") (pinfunction "D_PAD") (pintype "bidirectional"))
      (node (ref "Q13") (pin "P$5") (pinfunction "D_P$5") (pintype "bidirectional"))
      (node (ref "Q13") (pin "P$6") (pinfunction "D_P$6") (pintype "bidirectional"))
      (node (ref "Q13") (pin "P$7") (pinfunction "D_P$7") (pintype "bidirectional"))
      (node (ref "Q13") (pin "P$8") (pinfunction "D_P$8") (pintype "bidirectional"))
      (node (ref "Q13") (pin "PAD") (pinfunction "D_PAD") (pintype "bidirectional"))
    )
    (net (code "46") (name "Net-(Q12-G)") (class "Default")
      (node (ref "Q12") (pin "P$4") (pinfunction "G_P$4") (pintype "bidirectional"))
      (node (ref "R27") (pin "2") (pinfunction "2_2") (pintype "passive"))
      (node (ref "R29") (pin "1") (pinfunction "1_1") (pintype "passive"))
    )
    (net (code "47") (name "Net-(Q13-G)") (class "Default")
      (node (ref "Q13") (pin "P$4") (pinfunction "G_P$4") (pintype "bidirectional"))
      (node (ref "R28") (pin "2") (pinfunction "2_2") (pintype "passive"))
      (node (ref "R30") (pin "1") (pinfunction "1_1") (pintype "passive"))
    )
    (net (code "48") (name "Net-(Q14-G)") (class "Default")
      (node (ref "Q14") (pin "P$4") (pinfunction "G_P$4") (pintype "bidirectional"))
      (node (ref "U2") (pin "7") (pinfunction "HDRV_7") (pintype "passive"))
    )
    (net (code "49") (name "Net-(Q15-G)") (class "Default")
      (node (ref "Q15") (pin "P$4") (pinfunction "G_P$4") (pintype "bidirectional"))
      (node (ref "R44") (pin "1") (pinfunction "1_1") (pintype "passive"))
      (node (ref "U2") (pin "9") (pinfunction "LDRV/OC_9") (pintype "passive"))
    )
    (net (code "50") (name "Net-(U1-ACFET)") (class "Default")
      (node (ref "R19") (pin "1") (pinfunction "1_1") (pintype "passive"))
      (node (ref "U1") (pin "29") (pinfunction "ACFET_29") (pintype "bidirectional"))
    )
    (net (code "51") (name "Net-(U1-ACP)") (class "Default")
      (node (ref "R16") (pin "1") (pinfunction "1_1") (pintype "passive"))
      (node (ref "U1") (pin "31") (pinfunction "ACP_31") (pintype "bidirectional"))
    )
    (net (code "52") (name "Net-(U1-AFEFUSE)") (class "Default")
      (node (ref "R5") (pin "2") (pinfunction "2_2") (pintype "passive"))
      (node (ref "U1") (pin "21") (pinfunction "AFEFUSE_21") (pintype "bidirectional"))
    )
    (net (code "53") (name "Net-(U1-CHG)") (class "Default")
      (node (ref "R27") (pin "1") (pinfunction "1_1") (pintype "passive"))
      (node (ref "U1") (pin "32") (pinfunction "CHG_32") (pintype "bidirectional"))
    )
    (net (code "54") (name "Net-(U1-DSG)") (class "Default")
      (node (ref "R28") (pin "1") (pinfunction "1_1") (pintype "passive"))
      (node (ref "U1") (pin "30") (pinfunction "DSG_30") (pintype "bidirectional"))
    )
    (net (code "55") (name "Net-(U1-GPIO0)") (class "Default")
      (node (ref "R39") (pin "1") (pinfunction "1_1") (pintype "passive"))
      (node (ref "U1") (pin "14") (pinfunction "GPIO0_14") (pintype "bidirectional"))
    )
    (net (code "56") (name "Net-(U1-GPIO1)") (class "Default")
      (node (ref "J4") (pin "11") (pinfunction "11_11") (pintype "bidirectional"))
      (node (ref "U1") (pin "15") (pinfunction "GPIO1_15") (pintype "bidirectional"))
    )
    (net (code "57") (name "Net-(U1-HSRN)") (class "Default")
      (node (ref "C22") (pin "2") (pinfunction "2_2") (pintype "passive"))
      (node (ref "C24") (pin "1") (pinfunction "1_1") (pintype "passive"))
      (node (ref "R31") (pin "P$4") (pinfunction "P$4_P$4") (pintype "bidirectional"))
      (node (ref "U1") (pin "19") (pinfunction "HSRN_19") (pintype "bidirectional"))
    )
    (net (code "58") (name "Net-(U1-HSRP)") (class "Default")
      (node (ref "C22") (pin "1") (pinfunction "1_1") (pintype "passive"))
      (node (ref "C23") (pin "1") (pinfunction "1_1") (pintype "passive"))
      (node (ref "R31") (pin "P$3") (pinfunction "P$3_P$3") (pintype "bidirectional"))
      (node (ref "U1") (pin "20") (pinfunction "HSRP_20") (pintype "bidirectional"))
    )
    (net (code "59") (name "Net-(U1-PBI)") (class "Default")
      (node (ref "C8") (pin "1") (pinfunction "1_1") (pintype "passive"))
      (node (ref "U1") (pin "2") (pinfunction "PBI_2") (pintype "bidirectional"))
    )
    (net (code "60") (name "Net-(U1-PH)") (class "Default")
      (node (ref "C21") (pin "2") (pinfunction "2_2") (pintype "passive"))
      (node (ref "L1") (pin "P$1") (pinfunction "P$1_P$1") (pintype "bidirectional"))
      (node (ref "Q8") (pin "P$1") (pinfunction "S_P$1") (pintype "bidirectional"))
      (node (ref "Q8") (pin "P$2") (pinfunction "S_P$2") (pintype "bidirectional"))
      (node (ref "Q8") (pin "P$3") (pinfunction "S_P$3") (pintype "bidirectional"))
      (node (ref "Q9") (pin "P$5") (pinfunction "D_P$5") (pintype "bidirectional"))
      (node (ref "Q9") (pin "P$6") (pinfunction "D_P$6") (pintype "bidirectional"))
      (node (ref "Q9") (pin "P$7") (pinfunction "D_P$7") (pintype "bidirectional"))
      (node (ref "Q9") (pin "P$8") (pinfunction "D_P$8") (pintype "bidirectional"))
      (node (ref "Q9") (pin "PAD") (pinfunction "D_PAD") (pintype "bidirectional"))
      (node (ref "U1") (pin "26") (pinfunction "PH_26") (pintype "bidirectional"))
    )
    (net (code "61") (name "Net-(U1-REGN)") (class "Default")
      (node (ref "C20") (pin "1") (pinfunction "1_1") (pintype "passive"))
      (node (ref "D2") (pin "1") (pinfunction "A_1") (pintype "passive"))
      (node (ref "D2") (pin "2") (pinfunction "A_2") (pintype "passive"))
      (node (ref "U1") (pin "23") (pinfunction "REGN_23") (pintype "bidirectional"))
    )
    (net (code "62") (name "Net-(U1-SMBC)") (class "Default")
      (node (ref "R37") (pin "1") (pinfunction "1_1") (pintype "passive"))
      (node (ref "U1") (pin "17") (pinfunction "SMBC_17") (pintype "bidirectional"))
    )
    (net (code "63") (name "Net-(U1-SMBD)") (class "Default")
      (node (ref "R35") (pin "1") (pinfunction "1_1") (pintype "passive"))
      (node (ref "U1") (pin "16") (pinfunction "SMBD_16") (pintype "bidirectional"))
    )
    (net (code "64") (name "Net-(U1-SRN)") (class "Default")
      (node (ref "C5") (pin "2") (pinfunction "2_2") (pintype "passive"))
      (node (ref "C6") (pin "2") (pinfunction "2_2") (pintype "passive"))
      (node (ref "R32") (pin "P$3") (pinfunction "P$3_P$3") (pintype "bidirectional"))
      (node (ref "U1") (pin "7") (pinfunction "SRN_7") (pintype "bidirectional"))
    )
    (net (code "65") (name "Net-(U1-SRP)") (class "Default")
      (node (ref "C5") (pin "1") (pinfunction "1_1") (pintype "passive"))
      (node (ref "C6") (pin "1") (pinfunction "1_1") (pintype "passive"))
      (node (ref "R32") (pin "P$4") (pinfunction "P$4_P$4") (pintype "bidirectional"))
      (node (ref "U1") (pin "8") (pinfunction "SRP_8") (pintype "bidirectional"))
    )
    (net (code "66") (name "Net-(U1-TS1)") (class "Default")
      (node (ref "J3") (pin "1") (pinfunction "1_1") (pintype "bidirectional"))
      (node (ref "R8") (pin "2") (pinfunction "2_2") (pintype "passive"))
      (node (ref "U1") (pin "10") (pinfunction "TS1_10") (pintype "bidirectional"))
    )
    (net (code "67") (name "Net-(U1-TS2)") (class "Default")
      (node (ref "J3") (pin "3") (pinfunction "3_3") (pintype "bidirectional"))
      (node (ref "R9") (pin "2") (pinfunction "2_2") (pintype "passive"))
      (node (ref "U1") (pin "11") (pinfunction "TS2_11") (pintype "bidirectional"))
    )
    (net (code "68") (name "Net-(U1-TS3)") (class "Default")
      (node (ref "J3") (pin "5") (pinfunction "5_5") (pintype "bidirectional"))
      (node (ref "R10") (pin "2") (pinfunction "2_2") (pintype "passive"))
      (node (ref "U1") (pin "12") (pinfunction "TS3_12") (pintype "bidirectional"))
    )
    (net (code "69") (name "Net-(U1-TS4)") (class "Default")
      (node (ref "J3") (pin "7") (pinfunction "7_7") (pintype "bidirectional"))
      (node (ref "R11") (pin "2") (pinfunction "2_2") (pintype "passive"))
      (node (ref "U1") (pin "13") (pinfunction "TS4_13") (pintype "bidirectional"))
    )
    (net (code "70") (name "Net-(U1-VC1)") (class "Default")
      (node (ref "C3") (pin "2") (pinfunction "2_2") (pintype "passive"))
      (node (ref "C4") (pin "1") (pinfunction "1_1") (pintype "passive"))
      (node (ref "R4") (pin "2") (pinfunction "2_2") (pintype "passive"))
      (node (ref "U1") (pin "6") (pinfunction "VC1_6") (pintype "bidirectional"))
    )
    (net (code "71") (name "Net-(U1-VC2)") (class "Default")
      (node (ref "C2") (pin "2") (pinfunction "2_2") (pintype "passive"))
      (node (ref "C3") (pin "1") (pinfunction "1_1") (pintype "passive"))
      (node (ref "R3") (pin "2") (pinfunction "2_2") (pintype "passive"))
      (node (ref "U1") (pin "5") (pinfunction "VC2_5") (pintype "bidirectional"))
    )
    (net (code "72") (name "Net-(U1-VC3)") (class "Default")
      (node (ref "C1") (pin "2") (pinfunction "2_2") (pintype "passive"))
      (node (ref "C2") (pin "1") (pinfunction "1_1") (pintype "passive"))
      (node (ref "R2") (pin "2") (pinfunction "2_2") (pintype "passive"))
      (node (ref "U1") (pin "4") (pinfunction "VC3_4") (pintype "bidirectional"))
    )
    (net (code "73") (name "Net-(U1-VC4)") (class "Default")
      (node (ref "C1") (pin "1") (pinfunction "1_1") (pintype "passive"))
      (node (ref "R1") (pin "2") (pinfunction "2_2") (pintype "passive"))
      (node (ref "U1") (pin "3") (pinfunction "VC4_3") (pintype "bidirectional"))
    )
    (net (code "74") (name "Net-(U1-VCC)") (class "Default")
      (node (ref "C17") (pin "1") (pinfunction "1_1") (pintype "passive"))
      (node (ref "R23") (pin "1") (pinfunction "1_1") (pintype "passive"))
      (node (ref "U1") (pin "22") (pinfunction "VCC_22") (pintype "bidirectional"))
    )
    (net (code "75") (name "Net-(U1-VFB)") (class "Default")
      (node (ref "C27") (pin "2") (pinfunction "2_2") (pintype "passive"))
      (node (ref "R33") (pin "1") (pinfunction "1_1") (pintype "passive"))
      (node (ref "R34") (pin "2") (pinfunction "2_2") (pintype "passive"))
      (node (ref "U1") (pin "18") (pinfunction "VFB_18") (pintype "bidirectional"))
    )
    (net (code "76") (name "Net-(U2-BOOT)") (class "Default")
      (node (ref "C34") (pin "1") (pinfunction "1_1") (pintype "passive"))
      (node (ref "U2") (pin "6") (pinfunction "BOOT_6") (pintype "passive"))
    )
    (net (code "77") (name "Net-(U2-BP)") (class "Default")
      (node (ref "C33") (pin "1") (pinfunction "1_1") (pintype "passive"))
      (node (ref "R13") (pin "2") (pinfunction "2_2") (pintype "passive"))
      (node (ref "U2") (pin "10") (pinfunction "BP_10") (pintype "passive"))
    )
    (net (code "78") (name "Net-(U2-COMP)") (class "Default")
      (node (ref "C31") (pin "1") (pinfunction "1_1") (pintype "passive"))
      (node (ref "C32") (pin "1") (pinfunction "1_1") (pintype "passive"))
      (node (ref "U2") (pin "4") (pinfunction "COMP_4") (pintype "passive"))
    )
    (net (code "79") (name "Net-(U2-EN{slash}SS)") (class "Default")
      (node (ref "C30") (pin "1") (pinfunction "1_1") (pintype "passive"))
      (node (ref "U2") (pin "2") (pinfunction "EN/SS_2") (pintype "passive"))
    )
    (net (code "80") (name "Net-(U2-FB)") (class "Default")
      (node (ref "C31") (pin "2") (pinfunction "2_2") (pintype "passive"))
      (node (ref "C35") (pin "2") (pinfunction "2_2") (pintype "passive"))
      (node (ref "R12") (pin "1") (pinfunction "1_1") (pintype "passive"))
      (node (ref "R15") (pin "1") (pinfunction "1_1") (pintype "passive"))
      (node (ref "R43") (pin "2") (pinfunction "2_2") (pintype "passive"))
      (node (ref "U2") (pin "5") (pinfunction "FB_5") (pintype "passive"))
    )
    (net (code "81") (name "Net-(U2-PGOOD)") (class "Default")
      (node (ref "R13") (pin "1") (pinfunction "1_1") (pintype "passive"))
      (node (ref "U2") (pin "3") (pinfunction "PGOOD_3") (pintype "passive"))
    )
    (net (code "82") (name "Net-(U2-SW)") (class "Default")
      (node (ref "C34") (pin "2") (pinfunction "2_2") (pintype "passive"))
      (node (ref "L2") (pin "P$1") (pinfunction "P$1_P$1") (pintype "bidirectional"))
      (node (ref "Q14") (pin "P$1") (pinfunction "S_P$1") (pintype "bidirectional"))
      (node (ref "Q14") (pin "P$2") (pinfunction "S_P$2") (pintype "bidirectional"))
      (node (ref "Q14") (pin "P$3") (pinfunction "S_P$3") (pintype "bidirectional"))
      (node (ref "Q15") (pin "P$5") (pinfunction "D_P$5") (pintype "bidirectional"))
      (node (ref "Q15") (pin "P$6") (pinfunction "D_P$6") (pintype "bidirectional"))
      (node (ref "Q15") (pin "P$7") (pinfunction "D_P$7") (pintype "bidirectional"))
      (node (ref "Q15") (pin "P$8") (pinfunction "D_P$8") (pintype "bidirectional"))
      (node (ref "Q15") (pin "PAD") (pinfunction "D_PAD") (pintype "bidirectional"))
      (node (ref "U2") (pin "8") (pinfunction "SW_8") (pintype "passive"))
    )
    (net (code "83") (name "unconnected-(PCB1-PadP8.1)") (class "Default")
      (node (ref "PCB1") (pin "P8.1") (pinfunction "P8.1_P8.1") (pintype "bidirectional"))
    )
    (net (code "84") (name "unconnected-(PCB1-PadP8.2)") (class "Default")
      (node (ref "PCB1") (pin "P8.2") (pinfunction "P8.2_P8.2") (pintype "bidirectional"))
    )
    (net (code "85") (name "unconnected-(PCB1-PadP8.3)") (class "Default")
      (node (ref "PCB1") (pin "P8.3") (pinfunction "P8.3_P8.3") (pintype "bidirectional"))
    )
    (net (code "86") (name "unconnected-(PCB1-PadP8.4)") (class "Default")
      (node (ref "PCB1") (pin "P8.4") (pinfunction "P8.4_P8.4") (pintype "bidirectional"))
    )
    (net (code "87") (name "unconnected-(PCB1-PadP8.5)") (class "Default")
      (node (ref "PCB1") (pin "P8.5") (pinfunction "P8.5_P8.5") (pintype "bidirectional"))
    )
    (net (code "88") (name "unconnected-(PCB1-PadP8.6)") (class "Default")
      (node (ref "PCB1") (pin "P8.6") (pinfunction "P8.6_P8.6") (pintype "bidirectional"))
    )
    (net (code "89") (name "unconnected-(PCB1-PadP8.7)") (class "Default")
      (node (ref "PCB1") (pin "P8.7") (pinfunction "P8.7_P8.7") (pintype "bidirectional"))
    )
    (net (code "90") (name "unconnected-(PCB1-PadP8.8)") (class "Default")
      (node (ref "PCB1") (pin "P8.8") (pinfunction "P8.8_P8.8") (pintype "bidirectional"))
    )
    (net (code "91") (name "unconnected-(PCB1-PadP8.9)") (class "Default")
      (node (ref "PCB1") (pin "P8.9") (pinfunction "P8.9_P8.9") (pintype "bidirectional"))
    )
    (net (code "92") (name "unconnected-(PCB1-PadP8.10)") (class "Default")
      (node (ref "PCB1") (pin "P8.10") (pinfunction "P8.10_P8.10") (pintype "bidirectional"))
    )
    (net (code "93") (name "unconnected-(PCB1-PadP8.11)") (class "Default")
      (node (ref "PCB1") (pin "P8.11") (pinfunction "P8.11_P8.11") (pintype "bidirectional"))
    )
    (net (code "94") (name "unconnected-(PCB1-PadP8.12)") (class "Default")
      (node (ref "PCB1") (pin "P8.12") (pinfunction "P8.12_P8.12") (pintype "bidirectional"))
    )
    (net (code "95") (name "unconnected-(PCB1-PadP8.13)") (class "Default")
      (node (ref "PCB1") (pin "P8.13") (pinfunction "P8.13_P8.13") (pintype "bidirectional"))
    )
    (net (code "96") (name "unconnected-(PCB1-PadP8.14)") (class "Default")
      (node (ref "PCB1") (pin "P8.14") (pinfunction "P8.14_P8.14") (pintype "bidirectional"))
    )
    (net (code "97") (name "unconnected-(PCB1-PadP8.15)") (class "Default")
      (node (ref "PCB1") (pin "P8.15") (pinfunction "P8.15_P8.15") (pintype "bidirectional"))
    )
    (net (code "98") (name "unconnected-(PCB1-PadP8.16)") (class "Default")
      (node (ref "PCB1") (pin "P8.16") (pinfunction "P8.16_P8.16") (pintype "bidirectional"))
    )
    (net (code "99") (name "unconnected-(PCB1-PadP8.17)") (class "Default")
      (node (ref "PCB1") (pin "P8.17") (pinfunction "P8.17_P8.17") (pintype "bidirectional"))
    )
    (net (code "100") (name "unconnected-(PCB1-PadP8.18)") (class "Default")
      (node (ref "PCB1") (pin "P8.18") (pinfunction "P8.18_P8.18") (pintype "bidirectional"))
    )
    (net (code "101") (name "unconnected-(PCB1-PadP8.19)") (class "Default")
      (node (ref "PCB1") (pin "P8.19") (pinfunction "P8.19_P8.19") (pintype "bidirectional"))
    )
    (net (code "102") (name "unconnected-(PCB1-PadP8.20)") (class "Default")
      (node (ref "PCB1") (pin "P8.20") (pinfunction "P8.20_P8.20") (pintype "bidirectional"))
    )
    (net (code "103") (name "unconnected-(PCB1-PadP8.21)") (class "Default")
      (node (ref "PCB1") (pin "P8.21") (pinfunction "P8.21_P8.21") (pintype "bidirectional"))
    )
    (net (code "104") (name "unconnected-(PCB1-PadP8.22)") (class "Default")
      (node (ref "PCB1") (pin "P8.22") (pinfunction "P8.22_P8.22") (pintype "bidirectional"))
    )
    (net (code "105") (name "unconnected-(PCB1-PadP8.23)") (class "Default")
      (node (ref "PCB1") (pin "P8.23") (pinfunction "P8.23_P8.23") (pintype "bidirectional"))
    )
    (net (code "106") (name "unconnected-(PCB1-PadP8.24)") (class "Default")
      (node (ref "PCB1") (pin "P8.24") (pinfunction "P8.24_P8.24") (pintype "bidirectional"))
    )
    (net (code "107") (name "unconnected-(PCB1-PadP8.25)") (class "Default")
      (node (ref "PCB1") (pin "P8.25") (pinfunction "P8.25_P8.25") (pintype "bidirectional"))
    )
    (net (code "108") (name "unconnected-(PCB1-PadP8.26)") (class "Default")
      (node (ref "PCB1") (pin "P8.26") (pinfunction "P8.26_P8.26") (pintype "bidirectional"))
    )
    (net (code "109") (name "unconnected-(PCB1-PadP8.27)") (class "Default")
      (node (ref "PCB1") (pin "P8.27") (pinfunction "P8.27_P8.27") (pintype "bidirectional"))
    )
    (net (code "110") (name "unconnected-(PCB1-PadP8.28)") (class "Default")
      (node (ref "PCB1") (pin "P8.28") (pinfunction "P8.28_P8.28") (pintype "bidirectional"))
    )
    (net (code "111") (name "unconnected-(PCB1-PadP8.29)") (class "Default")
      (node (ref "PCB1") (pin "P8.29") (pinfunction "P8.29_P8.29") (pintype "bidirectional"))
    )
    (net (code "112") (name "unconnected-(PCB1-PadP8.30)") (class "Default")
      (node (ref "PCB1") (pin "P8.30") (pinfunction "P8.30_P8.30") (pintype "bidirectional"))
    )
    (net (code "113") (name "unconnected-(PCB1-PadP8.31)") (class "Default")
      (node (ref "PCB1") (pin "P8.31") (pinfunction "P8.31_P8.31") (pintype "bidirectional"))
    )
    (net (code "114") (name "unconnected-(PCB1-PadP8.32)") (class "Default")
      (node (ref "PCB1") (pin "P8.32") (pinfunction "P8.32_P8.32") (pintype "bidirectional"))
    )
    (net (code "115") (name "unconnected-(PCB1-PadP8.33)") (class "Default")
      (node (ref "PCB1") (pin "P8.33") (pinfunction "P8.33_P8.33") (pintype "bidirectional"))
    )
    (net (code "116") (name "unconnected-(PCB1-PadP8.34)") (class "Default")
      (node (ref "PCB1") (pin "P8.34") (pinfunction "P8.34_P8.34") (pintype "bidirectional"))
    )
    (net (code "117") (name "unconnected-(PCB1-PadP8.35)") (class "Default")
      (node (ref "PCB1") (pin "P8.35") (pinfunction "P8.35_P8.35") (pintype "bidirectional"))
    )
    (net (code "118") (name "unconnected-(PCB1-PadP8.36)") (class "Default")
      (node (ref "PCB1") (pin "P8.36") (pinfunction "P8.36_P8.36") (pintype "bidirectional"))
    )
    (net (code "119") (name "unconnected-(PCB1-PadP8.37)") (class "Default")
      (node (ref "PCB1") (pin "P8.37") (pinfunction "P8.37_P8.37") (pintype "bidirectional"))
    )
    (net (code "120") (name "unconnected-(PCB1-PadP8.38)") (class "Default")
      (node (ref "PCB1") (pin "P8.38") (pinfunction "P8.38_P8.38") (pintype "bidirectional"))
    )
    (net (code "121") (name "unconnected-(PCB1-PadP8.39)") (class "Default")
      (node (ref "PCB1") (pin "P8.39") (pinfunction "P8.39_P8.39") (pintype "bidirectional"))
    )
    (net (code "122") (name "unconnected-(PCB1-PadP8.40)") (class "Default")
      (node (ref "PCB1") (pin "P8.40") (pinfunction "P8.40_P8.40") (pintype "bidirectional"))
    )
    (net (code "123") (name "unconnected-(PCB1-PadP8.41)") (class "Default")
      (node (ref "PCB1") (pin "P8.41") (pinfunction "P8.41_P8.41") (pintype "bidirectional"))
    )
    (net (code "124") (name "unconnected-(PCB1-PadP8.42)") (class "Default")
      (node (ref "PCB1") (pin "P8.42") (pinfunction "P8.42_P8.42") (pintype "bidirectional"))
    )
    (net (code "125") (name "unconnected-(PCB1-PadP8.43)") (class "Default")
      (node (ref "PCB1") (pin "P8.43") (pinfunction "P8.43_P8.43") (pintype "bidirectional"))
    )
    (net (code "126") (name "unconnected-(PCB1-PadP8.44)") (class "Default")
      (node (ref "PCB1") (pin "P8.44") (pinfunction "P8.44_P8.44") (pintype "bidirectional"))
    )
    (net (code "127") (name "unconnected-(PCB1-PadP8.45)") (class "Default")
      (node (ref "PCB1") (pin "P8.45") (pinfunction "P8.45_P8.45") (pintype "bidirectional"))
    )
    (net (code "128") (name "unconnected-(PCB1-PadP8.46)") (class "Default")
      (node (ref "PCB1") (pin "P8.46") (pinfunction "P8.46_P8.46") (pintype "bidirectional"))
    )
    (net (code "129") (name "unconnected-(PCB1-PadP9.7)") (class "Default")
      (node (ref "PCB1") (pin "P9.7") (pinfunction "P9.7_P9.7") (pintype "bidirectional"))
    )
    (net (code "130") (name "unconnected-(PCB1-PadP9.8)") (class "Default")
      (node (ref "PCB1") (pin "P9.8") (pinfunction "P9.8_P9.8") (pintype "bidirectional"))
    )
    (net (code "131") (name "unconnected-(PCB1-PadP9.9)") (class "Default")
      (node (ref "PCB1") (pin "P9.9") (pinfunction "P9.9_P9.9") (pintype "bidirectional"))
    )
    (net (code "132") (name "unconnected-(PCB1-PadP9.10)") (class "Default")
      (node (ref "PCB1") (pin "P9.10") (pinfunction "P9.10_P9.10") (pintype "bidirectional"))
    )
    (net (code "133") (name "unconnected-(PCB1-PadP9.11)") (class "Default")
      (node (ref "PCB1") (pin "P9.11") (pinfunction "P9.11_P9.11") (pintype "bidirectional"))
    )
    (net (code "134") (name "unconnected-(PCB1-PadP9.12)") (class "Default")
      (node (ref "PCB1") (pin "P9.12") (pinfunction "P9.12_P9.12") (pintype "bidirectional"))
    )
    (net (code "135") (name "unconnected-(PCB1-PadP9.13)") (class "Default")
      (node (ref "PCB1") (pin "P9.13") (pinfunction "P9.13_P9.13") (pintype "bidirectional"))
    )
    (net (code "136") (name "unconnected-(PCB1-PadP9.14)") (class "Default")
      (node (ref "PCB1") (pin "P9.14") (pinfunction "P9.14_P9.14") (pintype "bidirectional"))
    )
    (net (code "137") (name "unconnected-(PCB1-PadP9.15)") (class "Default")
      (node (ref "PCB1") (pin "P9.15") (pinfunction "P9.15_P9.15") (pintype "bidirectional"))
    )
    (net (code "138") (name "unconnected-(PCB1-PadP9.16)") (class "Default")
      (node (ref "PCB1") (pin "P9.16") (pinfunction "P9.16_P9.16") (pintype "bidirectional"))
    )
    (net (code "139") (name "unconnected-(PCB1-PadP9.17)") (class "Default")
      (node (ref "PCB1") (pin "P9.17") (pinfunction "P9.17_P9.17") (pintype "bidirectional"))
    )
    (net (code "140") (name "unconnected-(PCB1-PadP9.18)") (class "Default")
      (node (ref "PCB1") (pin "P9.18") (pinfunction "P9.18_P9.18") (pintype "bidirectional"))
    )
    (net (code "141") (name "unconnected-(PCB1-PadP9.19)") (class "Default")
      (node (ref "PCB1") (pin "P9.19") (pinfunction "P9.19_P9.19") (pintype "bidirectional"))
    )
    (net (code "142") (name "unconnected-(PCB1-PadP9.20)") (class "Default")
      (node (ref "PCB1") (pin "P9.20") (pinfunction "P9.20_P9.20") (pintype "bidirectional"))
    )
    (net (code "143") (name "unconnected-(PCB1-PadP9.21)") (class "Default")
      (node (ref "PCB1") (pin "P9.21") (pinfunction "P9.21_P9.21") (pintype "bidirectional"))
    )
    (net (code "144") (name "unconnected-(PCB1-PadP9.22)") (class "Default")
      (node (ref "PCB1") (pin "P9.22") (pinfunction "P9.22_P9.22") (pintype "bidirectional"))
    )
    (net (code "145") (name "unconnected-(PCB1-PadP9.23)") (class "Default")
      (node (ref "PCB1") (pin "P9.23") (pinfunction "P9.23_P9.23") (pintype "bidirectional"))
    )
    (net (code "146") (name "unconnected-(PCB1-PadP9.25)") (class "Default")
      (node (ref "PCB1") (pin "P9.25") (pinfunction "P9.25_P9.25") (pintype "bidirectional"))
    )
    (net (code "147") (name "unconnected-(PCB1-PadP9.27)") (class "Default")
      (node (ref "PCB1") (pin "P9.27") (pinfunction "P9.27_P9.27") (pintype "bidirectional"))
    )
    (net (code "148") (name "unconnected-(PCB1-PadP9.28)") (class "Default")
      (node (ref "PCB1") (pin "P9.28") (pinfunction "P9.28_P9.28") (pintype "bidirectional"))
    )
    (net (code "149") (name "unconnected-(PCB1-PadP9.29)") (class "Default")
      (node (ref "PCB1") (pin "P9.29") (pinfunction "P9.29_P9.29") (pintype "bidirectional"))
    )
    (net (code "150") (name "unconnected-(PCB1-PadP9.30)") (class "Default")
      (node (ref "PCB1") (pin "P9.30") (pinfunction "P9.30_P9.30") (pintype "bidirectional"))
    )
    (net (code "151") (name "unconnected-(PCB1-PadP9.31)") (class "Default")
      (node (ref "PCB1") (pin "P9.31") (pinfunction "P9.31_P9.31") (pintype "bidirectional"))
    )
    (net (code "152") (name "unconnected-(PCB1-PadP9.32)") (class "Default")
      (node (ref "PCB1") (pin "P9.32") (pinfunction "P9.32_P9.32") (pintype "bidirectional"))
    )
    (net (code "153") (name "unconnected-(PCB1-PadP9.33)") (class "Default")
      (node (ref "PCB1") (pin "P9.33") (pinfunction "P9.33_P9.33") (pintype "bidirectional"))
    )
    (net (code "154") (name "unconnected-(PCB1-PadP9.34)") (class "Default")
      (node (ref "PCB1") (pin "P9.34") (pinfunction "P9.34_P9.34") (pintype "bidirectional"))
    )
    (net (code "155") (name "unconnected-(PCB1-PadP9.35)") (class "Default")
      (node (ref "PCB1") (pin "P9.35") (pinfunction "P9.35_P9.35") (pintype "bidirectional"))
    )
    (net (code "156") (name "unconnected-(PCB1-PadP9.36)") (class "Default")
      (node (ref "PCB1") (pin "P9.36") (pinfunction "P9.36_P9.36") (pintype "bidirectional"))
    )
    (net (code "157") (name "unconnected-(PCB1-PadP9.37)") (class "Default")
      (node (ref "PCB1") (pin "P9.37") (pinfunction "P9.37_P9.37") (pintype "bidirectional"))
    )
    (net (code "158") (name "unconnected-(PCB1-PadP9.38)") (class "Default")
      (node (ref "PCB1") (pin "P9.38") (pinfunction "P9.38_P9.38") (pintype "bidirectional"))
    )
    (net (code "159") (name "unconnected-(PCB1-PadP9.39)") (class "Default")
      (node (ref "PCB1") (pin "P9.39") (pinfunction "P9.39_P9.39") (pintype "bidirectional"))
    )
    (net (code "160") (name "unconnected-(PCB1-PadP9.40)") (class "Default")
      (node (ref "PCB1") (pin "P9.40") (pinfunction "P9.40_P9.40") (pintype "bidirectional"))
    )
    (net (code "161") (name "unconnected-(PCB1-PadP9.41)") (class "Default")
      (node (ref "PCB1") (pin "P9.41") (pinfunction "P9.41_P9.41") (pintype "bidirectional"))
    )
    (net (code "162") (name "unconnected-(PCB1-PadP9.42)") (class "Default")
      (node (ref "PCB1") (pin "P9.42") (pinfunction "P9.42_P9.42") (pintype "bidirectional"))
    )
  )
)
